# lab2_yakimenko_boost.net
KiCad netlist of a schematic drawn in Altium Designer
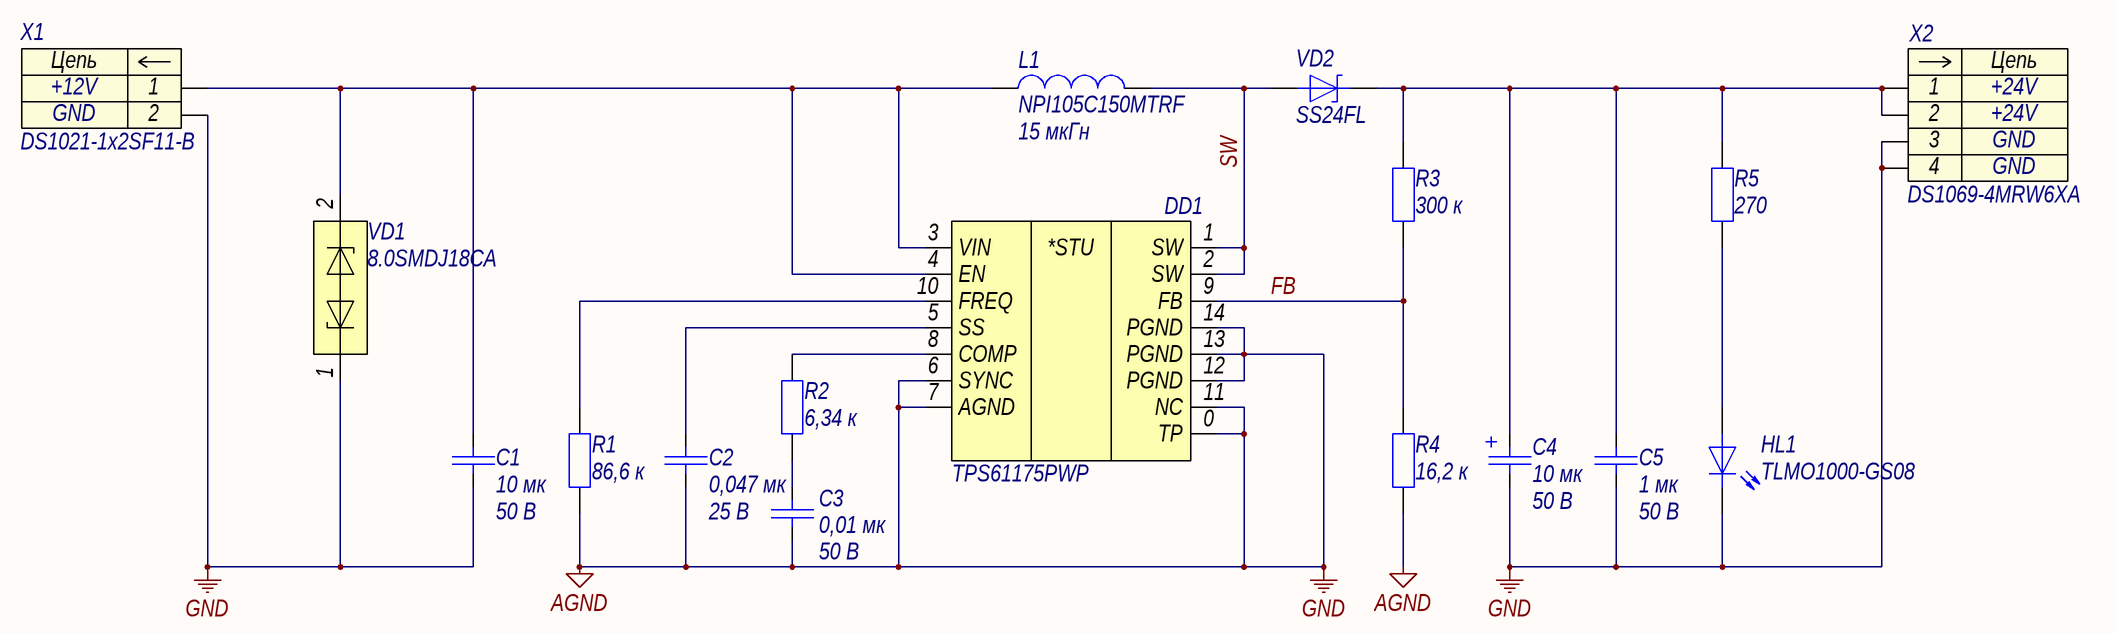
[diagram p0: lab2_yakimenko_boost.SchDoc]

(export (version "E")
  (design (tool "Eeschema 10.0.6"))
  (components
    (comp (ref "C1")
      (value "10 мк")
      (footprint "C0805")
      (description "=Описание")
      (fields (field (name "НАПРЯЖЕНИЕ") "50 В"))
      (libsource (lib "Database_Students") (part "C-NONPOLAR"))
    )
    (comp (ref "C2")
      (value "0,047 мк")
      (footprint "C0603")
      (description "=Описание")
      (fields (field (name "НАПРЯЖЕНИЕ") "25 В"))
      (libsource (lib "Database_Students") (part "C-NONPOLAR"))
    )
    (comp (ref "C3")
      (value "0,01 мк")
      (footprint "C0603")
      (description "=Описание")
      (fields (field (name "НАПРЯЖЕНИЕ") "50 В"))
      (libsource (lib "Database_Students") (part "C-NONPOLAR"))
    )
    (comp (ref "C4")
      (value "10 мк")
      (footprint "SVPF10M")
      (description "=Описание")
      (fields (field (name "НАПРЯЖЕНИЕ") "50 В"))
      (libsource (lib "Database_Students") (part "C-POLAR"))
    )
    (comp (ref "C5")
      (value "1 мк")
      (footprint "C0603")
      (description "=Описание")
      (fields (field (name "НАПРЯЖЕНИЕ") "50 В"))
      (libsource (lib "Database_Students") (part "C-NONPOLAR"))
    )
    (comp (ref "DD1")
      (value "TPS61175PWP")
      (footprint "HTSSOP-14")
      (description "=Описание")
      (libsource (lib "Database_Students") (part "TPS61175PWP"))
    )
    (comp (ref "HL1")
      (value "TLMO1000-GS08")
      (footprint "HL0603")
      (description "=Описание")
      (libsource (lib "Database_Students") (part "HL-COMMON"))
    )
    (comp (ref "L1")
      (value "NPI105C150MTRF")
      (footprint "NPI-2-1000X900X540")
      (description "=Описание")
      (fields (field (name "ИНДУКТИВНОСТЬ") "15 мкГн"))
      (libsource (lib "Database_Students") (part "INDUCTOR-COMMON"))
    )
    (comp (ref "R1")
      (value "86,6 к")
      (footprint "R0603")
      (description "=Описание")
      (libsource (lib "Database_Students") (part "R-COMMON"))
    )
    (comp (ref "R2")
      (value "6,34 к")
      (footprint "R0603")
      (description "=Описание")
      (libsource (lib "Database_Students") (part "R-COMMON"))
    )
    (comp (ref "R3")
      (value "300 к")
      (footprint "R0603")
      (description "=Описание")
      (libsource (lib "Database_Students") (part "R-COMMON"))
    )
    (comp (ref "R4")
      (value "16,2 к")
      (footprint "R0603")
      (description "=Описание")
      (libsource (lib "Database_Students") (part "R-COMMON"))
    )
    (comp (ref "R5")
      (value "270")
      (footprint "R0603")
      (description "=Описание")
      (libsource (lib "Database_Students") (part "R-COMMON"))
    )
    (comp (ref "VD1")
      (value "8.0SMDJ18CA")
      (footprint "DO-214AB")
      (description "=Описание")
      (libsource (lib "Database_Students") (part "ZENER-BI-DIRECTIONAL"))
    )
    (comp (ref "VD2")
      (value "SS24FL")
      (footprint "SOD123")
      (description "=Описание")
      (libsource (lib "Database_Students") (part "DIODE-SCHOTTKY"))
    )
    (comp (ref "X1")
      (value "DS1021-1x2SF11-B")
      (footprint "DS1021-1X2SF11-B")
      (description "=Описание")
      (libsource (lib "Database_Students") (part "HEADER-2-PLG"))
    )
    (comp (ref "X2")
      (value "DS1069-4MRW6XA")
      (footprint "HDR1X4")
      (description "=Описание")
      (libsource (lib "Database_Students") (part "HEADER-4-PLG"))
    )
  )
  (nets
    (net (code "1") (name "/FB") (class "Default")
      (node (ref "DD1") (pin "9") (pinfunction "FB_9") (pintype "passive"))
      (node (ref "R3") (pin "1") (pinfunction "1_1") (pintype "passive"))
      (node (ref "R4") (pin "2") (pinfunction "2_2") (pintype "passive"))
    )
    (net (code "2") (name "/SW") (class "Default")
      (node (ref "DD1") (pin "1") (pinfunction "SW_1") (pintype "passive"))
      (node (ref "DD1") (pin "2") (pinfunction "SW_2") (pintype "passive"))
      (node (ref "L1") (pin "2") (pinfunction "2_2") (pintype "passive"))
      (node (ref "VD2") (pin "2") (pinfunction "2_2") (pintype "passive"))
    )
    (net (code "3") (name "AGND") (class "Default")
      (node (ref "C1") (pin "2") (pinfunction "2_2") (pintype "passive"))
      (node (ref "C2") (pin "2") (pinfunction "2_2") (pintype "passive"))
      (node (ref "C3") (pin "2") (pinfunction "2_2") (pintype "passive"))
      (node (ref "C4") (pin "2") (pinfunction "2_2") (pintype "passive"))
      (node (ref "C5") (pin "2") (pinfunction "2_2") (pintype "passive"))
      (node (ref "DD1") (pin "0") (pinfunction "TP_0") (pintype "passive"))
      (node (ref "DD1") (pin "11") (pinfunction "NC_11") (pintype "passive"))
      (node (ref "DD1") (pin "12") (pinfunction "PGND_12") (pintype "passive"))
      (node (ref "DD1") (pin "13") (pinfunction "PGND_13") (pintype "passive"))
      (node (ref "DD1") (pin "14") (pinfunction "PGND_14") (pintype "passive"))
      (node (ref "DD1") (pin "6") (pinfunction "SYNC_6") (pintype "passive"))
      (node (ref "DD1") (pin "7") (pinfunction "AGND_7") (pintype "passive"))
      (node (ref "HL1") (pin "1") (pinfunction "1_1") (pintype "passive"))
      (node (ref "R1") (pin "1") (pinfunction "1_1") (pintype "passive"))
      (node (ref "R4") (pin "1") (pinfunction "1_1") (pintype "passive"))
      (node (ref "VD1") (pin "1") (pinfunction "1_1") (pintype "passive"))
      (node (ref "X1") (pin "2") (pinfunction "2_2") (pintype "passive"))
      (node (ref "X2") (pin "3") (pinfunction "3_3") (pintype "passive"))
      (node (ref "X2") (pin "4") (pinfunction "4_4") (pintype "passive"))
    )
    (net (code "4") (name "Net-(C3-Pad1)") (class "Default")
      (node (ref "C3") (pin "1") (pinfunction "1_1") (pintype "passive"))
      (node (ref "R2") (pin "1") (pinfunction "1_1") (pintype "passive"))
    )
    (net (code "5") (name "Net-(C4-Pad1)") (class "Default")
      (node (ref "C4") (pin "1") (pinfunction "1_1") (pintype "passive"))
      (node (ref "C5") (pin "1") (pinfunction "1_1") (pintype "passive"))
      (node (ref "R3") (pin "2") (pinfunction "2_2") (pintype "passive"))
      (node (ref "R5") (pin "2") (pinfunction "2_2") (pintype "passive"))
      (node (ref "VD2") (pin "1") (pinfunction "1_1") (pintype "passive"))
      (node (ref "X2") (pin "1") (pinfunction "1_1") (pintype "passive"))
      (node (ref "X2") (pin "2") (pinfunction "2_2") (pintype "passive"))
    )
    (net (code "6") (name "Net-(DD1-COMP)") (class "Default")
      (node (ref "DD1") (pin "8") (pinfunction "COMP_8") (pintype "passive"))
      (node (ref "R2") (pin "2") (pinfunction "2_2") (pintype "passive"))
    )
    (net (code "7") (name "Net-(DD1-EN)") (class "Default")
      (node (ref "C1") (pin "1") (pinfunction "1_1") (pintype "passive"))
      (node (ref "DD1") (pin "3") (pinfunction "VIN_3") (pintype "passive"))
      (node (ref "DD1") (pin "4") (pinfunction "EN_4") (pintype "passive"))
      (node (ref "L1") (pin "1") (pinfunction "1_1") (pintype "passive"))
      (node (ref "VD1") (pin "2") (pinfunction "2_2") (pintype "passive"))
      (node (ref "X1") (pin "1") (pinfunction "1_1") (pintype "passive"))
    )
    (net (code "8") (name "Net-(DD1-FREQ)") (class "Default")
      (node (ref "DD1") (pin "10") (pinfunction "FREQ_10") (pintype "passive"))
      (node (ref "R1") (pin "2") (pinfunction "2_2") (pintype "passive"))
    )
    (net (code "9") (name "Net-(DD1-SS)") (class "Default")
      (node (ref "C2") (pin "1") (pinfunction "1_1") (pintype "passive"))
      (node (ref "DD1") (pin "5") (pinfunction "SS_5") (pintype "passive"))
    )
    (net (code "10") (name "Net-(HL1-Pad2)") (class "Default")
      (node (ref "HL1") (pin "2") (pinfunction "2_2") (pintype "passive"))
      (node (ref "R5") (pin "1") (pinfunction "1_1") (pintype "passive"))
    )
  )
)
